# MCU.net
KiCad netlist of a schematic drawn in EAGLE
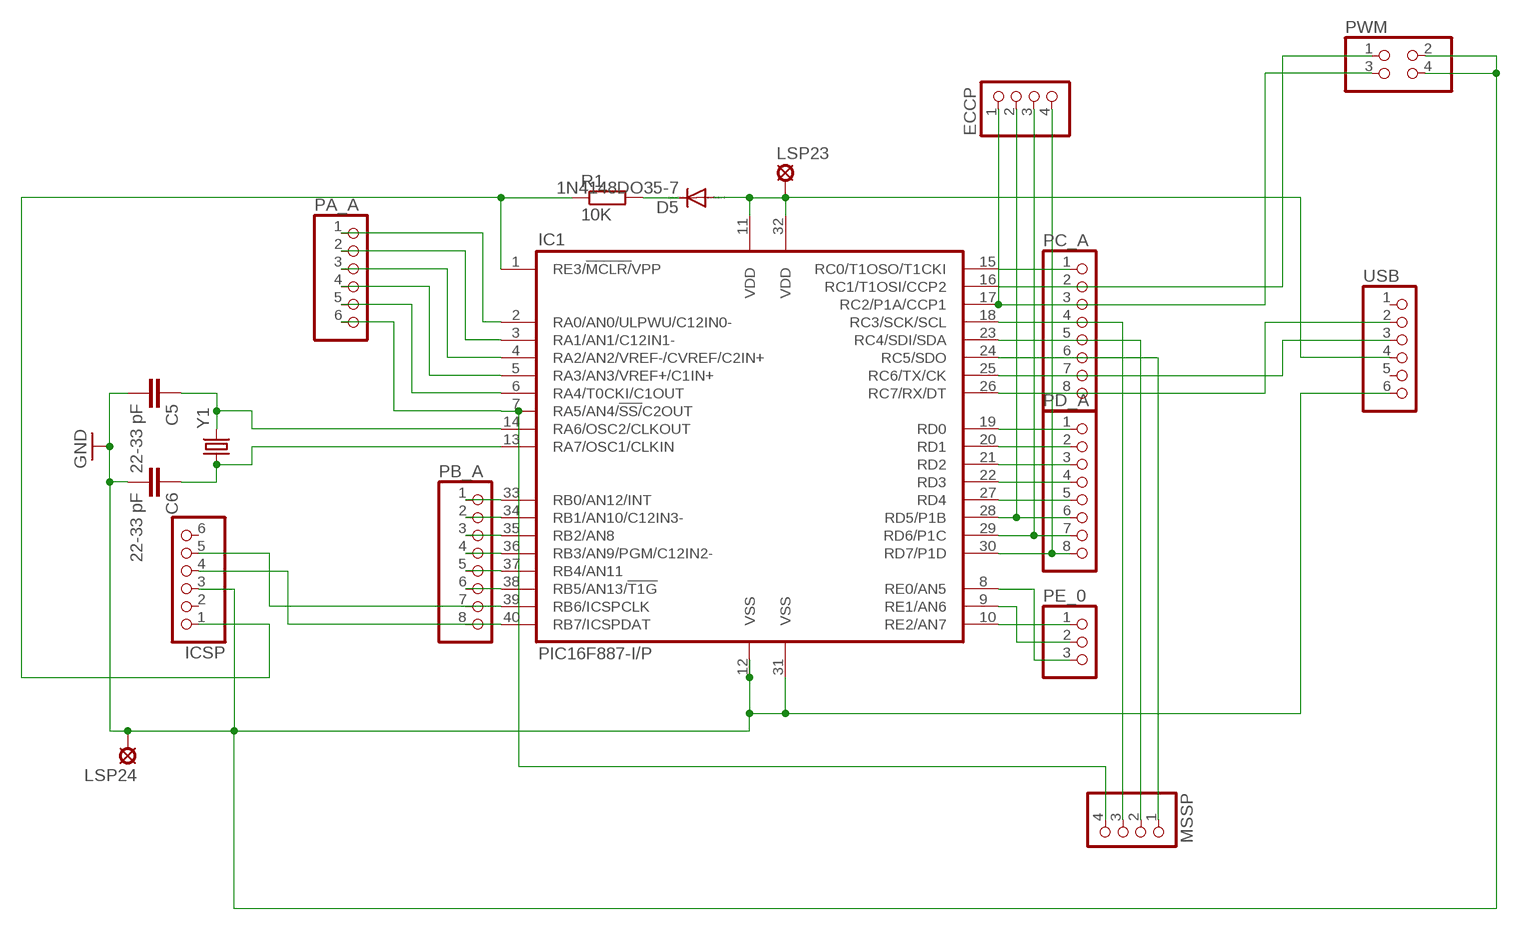
[diagram p0: schematic, sheet 1]

(export (version "E")
  (design (tool "Eeschema 10.0.6"))
  (components
    (comp (ref "C5")
      (value "22-33 pF")
      (footprint "eagle-import:C025-024X044")
      (libsource (lib "eagle-import") (part "C-EU025-024X044"))
    )
    (comp (ref "C6")
      (value "22-33 pF")
      (footprint "eagle-import:C025-024X044")
      (libsource (lib "eagle-import") (part "C-EU025-024X044"))
    )
    (comp (ref "D5")
      (value "1N4148DO35-7")
      (footprint "eagle-import:DO35-7")
      (libsource (lib "eagle-import") (part "1N4148DO35-7"))
    )
    (comp (ref "ECCP")
      (value "PINHD-1X4")
      (footprint "eagle-import:1X04")
      (libsource (lib "eagle-import") (part "PINHD-1X4"))
    )
    (comp (ref "IC1")
      (value "PIC16F887-I/P")
      (footprint "eagle-import:DIL40")
      (libsource (lib "eagle-import") (part "PIC16F887-I/P"))
    )
    (comp (ref "ICSP")
      (value "PINHD-1X6")
      (footprint "eagle-import:1X06")
      (libsource (lib "eagle-import") (part "PINHD-1X6"))
    )
    (comp (ref "LSP23")
      (value "LSP10")
      (footprint "eagle-import:LSP10")
      (libsource (lib "eagle-import") (part "LSP10"))
    )
    (comp (ref "LSP24")
      (value "LSP10")
      (footprint "eagle-import:LSP10")
      (libsource (lib "eagle-import") (part "LSP10"))
    )
    (comp (ref "MSSP")
      (value "PINHD-1X4")
      (footprint "eagle-import:1X04")
      (libsource (lib "eagle-import") (part "PINHD-1X4"))
    )
    (comp (ref "PA_A")
      (value "PINHD-1X6")
      (footprint "eagle-import:1X06")
      (libsource (lib "eagle-import") (part "PINHD-1X6"))
    )
    (comp (ref "PB_A")
      (value "PINHD-1X8")
      (footprint "eagle-import:1X08")
      (libsource (lib "eagle-import") (part "PINHD-1X8"))
    )
    (comp (ref "PC_A")
      (value "PINHD-1X8")
      (footprint "eagle-import:1X08")
      (libsource (lib "eagle-import") (part "PINHD-1X8"))
    )
    (comp (ref "PD_A")
      (value "PINHD-1X8")
      (footprint "eagle-import:1X08")
      (libsource (lib "eagle-import") (part "PINHD-1X8"))
    )
    (comp (ref "PE_0")
      (value "PINHD-1X3")
      (footprint "eagle-import:1X03")
      (libsource (lib "eagle-import") (part "PINHD-1X3"))
    )
    (comp (ref "PWM")
      (value "PINHD-2X2")
      (footprint "eagle-import:2X02")
      (libsource (lib "eagle-import") (part "PINHD-2X2"))
    )
    (comp (ref "R1")
      (value "10K")
      (footprint "eagle-import:0207_10")
      (libsource (lib "eagle-import") (part "R-EU_0207/10"))
    )
    (comp (ref "USB")
      (value "PINHD-1X6")
      (footprint "eagle-import:1X06")
      (libsource (lib "eagle-import") (part "PINHD-1X6"))
    )
    (comp (ref "Y1")
      (value "CRYSTALHC49UV")
      (footprint "eagle-import:HC49U-V")
      (libsource (lib "eagle-import") (part "CRYSTALHC49UV"))
    )
  )
  (nets
    (net (code "1") (name "GND") (class "Default")
      (node (ref "C5") (pin "2") (pinfunction "2_2") (pintype "passive"))
      (node (ref "C6") (pin "2") (pinfunction "2_2") (pintype "passive"))
      (node (ref "IC1") (pin "12") (pinfunction "VSS_12") (pintype "power_in"))
      (node (ref "IC1") (pin "31") (pinfunction "VSS_31") (pintype "power_in"))
      (node (ref "ICSP") (pin "3") (pinfunction "3_3") (pintype "passive"))
      (node (ref "LSP24") (pin "MP") (pinfunction "MP_MP") (pintype "passive"))
      (node (ref "PWM") (pin "2") (pinfunction "2_2") (pintype "passive"))
      (node (ref "PWM") (pin "4") (pinfunction "4_4") (pintype "passive"))
      (node (ref "USB") (pin "6") (pinfunction "6_6") (pintype "passive"))
    )
    (net (code "2") (name "Net-(D5-PadA)") (class "Default")
      (node (ref "D5") (pin "A") (pinfunction "A_A") (pintype "passive"))
      (node (ref "IC1") (pin "11") (pinfunction "VDD_11") (pintype "power_in"))
      (node (ref "IC1") (pin "32") (pinfunction "VDD_32") (pintype "power_in"))
      (node (ref "LSP23") (pin "MP") (pinfunction "MP_MP") (pintype "passive"))
      (node (ref "USB") (pin "4") (pinfunction "4_4") (pintype "passive"))
    )
    (net (code "3") (name "Net-(D5-PadC)") (class "Default")
      (node (ref "D5") (pin "C") (pinfunction "C_C") (pintype "passive"))
      (node (ref "R1") (pin "2") (pinfunction "2_2") (pintype "passive"))
    )
    (net (code "4") (name "Net-(IC1-RA0{slash}AN0{slash}ULPWU{slash}C12IN0-)") (class "Default")
      (node (ref "IC1") (pin "2") (pinfunction "RA0/AN0/ULPWU/C12IN0-_2") (pintype "bidirectional"))
      (node (ref "PA_A") (pin "1") (pinfunction "1_1") (pintype "passive"))
    )
    (net (code "5") (name "Net-(IC1-RA1{slash}AN1{slash}C12IN1-)") (class "Default")
      (node (ref "IC1") (pin "3") (pinfunction "RA1/AN1/C12IN1-_3") (pintype "bidirectional"))
      (node (ref "PA_A") (pin "2") (pinfunction "2_2") (pintype "passive"))
    )
    (net (code "6") (name "Net-(IC1-RA2{slash}AN2{slash}VREF-{slash}CVREF{slash}C2IN+)") (class "Default")
      (node (ref "IC1") (pin "4") (pinfunction "RA2/AN2/VREF-/CVREF/C2IN+_4") (pintype "bidirectional"))
      (node (ref "PA_A") (pin "3") (pinfunction "3_3") (pintype "passive"))
    )
    (net (code "7") (name "Net-(IC1-RA3{slash}AN3{slash}VREF+{slash}C1IN+)") (class "Default")
      (node (ref "IC1") (pin "5") (pinfunction "RA3/AN3/VREF+/C1IN+_5") (pintype "bidirectional"))
      (node (ref "PA_A") (pin "4") (pinfunction "4_4") (pintype "passive"))
    )
    (net (code "8") (name "Net-(IC1-RA4{slash}T0CKI{slash}C1OUT)") (class "Default")
      (node (ref "IC1") (pin "6") (pinfunction "RA4/T0CKI/C1OUT_6") (pintype "bidirectional"))
      (node (ref "PA_A") (pin "5") (pinfunction "5_5") (pintype "passive"))
    )
    (net (code "9") (name "Net-(IC1-RA5{slash}AN4{slash}~{SS{slash}}C2OUT)") (class "Default")
      (node (ref "IC1") (pin "7") (pinfunction "RA5/AN4/~{SS/}C2OUT_7") (pintype "bidirectional"))
      (node (ref "MSSP") (pin "4") (pinfunction "4_4") (pintype "passive"))
      (node (ref "PA_A") (pin "6") (pinfunction "6_6") (pintype "passive"))
    )
    (net (code "10") (name "Net-(IC1-RA6{slash}OSC2{slash}CLKOUT)") (class "Default")
      (node (ref "C5") (pin "1") (pinfunction "1_1") (pintype "passive"))
      (node (ref "IC1") (pin "14") (pinfunction "RA6/OSC2/CLKOUT_14") (pintype "bidirectional"))
      (node (ref "Y1") (pin "2") (pinfunction "2_2") (pintype "passive"))
    )
    (net (code "11") (name "Net-(IC1-RA7{slash}OSC1{slash}CLKIN)") (class "Default")
      (node (ref "C6") (pin "1") (pinfunction "1_1") (pintype "passive"))
      (node (ref "IC1") (pin "13") (pinfunction "RA7/OSC1/CLKIN_13") (pintype "bidirectional"))
      (node (ref "Y1") (pin "1") (pinfunction "1_1") (pintype "passive"))
    )
    (net (code "12") (name "Net-(IC1-RB0{slash}AN12{slash}INT)") (class "Default")
      (node (ref "IC1") (pin "33") (pinfunction "RB0/AN12/INT_33") (pintype "bidirectional"))
      (node (ref "PB_A") (pin "1") (pinfunction "1_1") (pintype "passive"))
    )
    (net (code "13") (name "Net-(IC1-RB1{slash}AN10{slash}C12IN3-)") (class "Default")
      (node (ref "IC1") (pin "34") (pinfunction "RB1/AN10/C12IN3-_34") (pintype "bidirectional"))
      (node (ref "PB_A") (pin "2") (pinfunction "2_2") (pintype "passive"))
    )
    (net (code "14") (name "Net-(IC1-RB2{slash}AN8)") (class "Default")
      (node (ref "IC1") (pin "35") (pinfunction "RB2/AN8_35") (pintype "bidirectional"))
      (node (ref "PB_A") (pin "3") (pinfunction "3_3") (pintype "passive"))
    )
    (net (code "15") (name "Net-(IC1-RB3{slash}AN9{slash}PGM{slash}C12IN2-)") (class "Default")
      (node (ref "IC1") (pin "36") (pinfunction "RB3/AN9/PGM/C12IN2-_36") (pintype "bidirectional"))
      (node (ref "PB_A") (pin "4") (pinfunction "4_4") (pintype "passive"))
    )
    (net (code "16") (name "Net-(IC1-RB4{slash}AN11)") (class "Default")
      (node (ref "IC1") (pin "37") (pinfunction "RB4/AN11_37") (pintype "bidirectional"))
      (node (ref "PB_A") (pin "5") (pinfunction "5_5") (pintype "passive"))
    )
    (net (code "17") (name "Net-(IC1-RB5{slash}AN13{slash}~{T1G})") (class "Default")
      (node (ref "IC1") (pin "38") (pinfunction "RB5/AN13/~{T1G}_38") (pintype "bidirectional"))
      (node (ref "PB_A") (pin "6") (pinfunction "6_6") (pintype "passive"))
    )
    (net (code "18") (name "Net-(IC1-RB6{slash}ICSPCLK)") (class "Default")
      (node (ref "IC1") (pin "39") (pinfunction "RB6/ICSPCLK_39") (pintype "bidirectional"))
      (node (ref "ICSP") (pin "5") (pinfunction "5_5") (pintype "passive"))
      (node (ref "PB_A") (pin "7") (pinfunction "7_7") (pintype "passive"))
    )
    (net (code "19") (name "Net-(IC1-RB7{slash}ICSPDAT)") (class "Default")
      (node (ref "IC1") (pin "40") (pinfunction "RB7/ICSPDAT_40") (pintype "bidirectional"))
      (node (ref "ICSP") (pin "4") (pinfunction "4_4") (pintype "passive"))
      (node (ref "PB_A") (pin "8") (pinfunction "8_8") (pintype "passive"))
    )
    (net (code "20") (name "Net-(IC1-RC0{slash}T1OSO{slash}T1CKI)") (class "Default")
      (node (ref "IC1") (pin "15") (pinfunction "RC0/T1OSO/T1CKI_15") (pintype "bidirectional"))
      (node (ref "PC_A") (pin "1") (pinfunction "1_1") (pintype "passive"))
    )
    (net (code "21") (name "Net-(IC1-RC1{slash}T1OSI{slash}CCP2)") (class "Default")
      (node (ref "IC1") (pin "16") (pinfunction "RC1/T1OSI/CCP2_16") (pintype "bidirectional"))
      (node (ref "PC_A") (pin "2") (pinfunction "2_2") (pintype "passive"))
      (node (ref "PWM") (pin "1") (pinfunction "1_1") (pintype "passive"))
    )
    (net (code "22") (name "Net-(IC1-RC2{slash}P1A{slash}CCP1)") (class "Default")
      (node (ref "ECCP") (pin "1") (pinfunction "1_1") (pintype "passive"))
      (node (ref "IC1") (pin "17") (pinfunction "RC2/P1A/CCP1_17") (pintype "bidirectional"))
      (node (ref "PC_A") (pin "3") (pinfunction "3_3") (pintype "passive"))
      (node (ref "PWM") (pin "3") (pinfunction "3_3") (pintype "passive"))
    )
    (net (code "23") (name "Net-(IC1-RC3{slash}SCK{slash}SCL)") (class "Default")
      (node (ref "IC1") (pin "18") (pinfunction "RC3/SCK/SCL_18") (pintype "bidirectional"))
      (node (ref "MSSP") (pin "3") (pinfunction "3_3") (pintype "passive"))
      (node (ref "PC_A") (pin "4") (pinfunction "4_4") (pintype "passive"))
    )
    (net (code "24") (name "Net-(IC1-RC4{slash}SDI{slash}SDA)") (class "Default")
      (node (ref "IC1") (pin "23") (pinfunction "RC4/SDI/SDA_23") (pintype "bidirectional"))
      (node (ref "MSSP") (pin "2") (pinfunction "2_2") (pintype "passive"))
      (node (ref "PC_A") (pin "5") (pinfunction "5_5") (pintype "passive"))
    )
    (net (code "25") (name "Net-(IC1-RC5{slash}SDO)") (class "Default")
      (node (ref "IC1") (pin "24") (pinfunction "RC5/SDO_24") (pintype "bidirectional"))
      (node (ref "MSSP") (pin "1") (pinfunction "1_1") (pintype "passive"))
      (node (ref "PC_A") (pin "6") (pinfunction "6_6") (pintype "passive"))
    )
    (net (code "26") (name "Net-(IC1-RC6{slash}TX{slash}CK)") (class "Default")
      (node (ref "IC1") (pin "25") (pinfunction "RC6/TX/CK_25") (pintype "bidirectional"))
      (node (ref "PC_A") (pin "7") (pinfunction "7_7") (pintype "passive"))
      (node (ref "USB") (pin "3") (pinfunction "3_3") (pintype "passive"))
    )
    (net (code "27") (name "Net-(IC1-RC7{slash}RX{slash}DT)") (class "Default")
      (node (ref "IC1") (pin "26") (pinfunction "RC7/RX/DT_26") (pintype "bidirectional"))
      (node (ref "PC_A") (pin "8") (pinfunction "8_8") (pintype "passive"))
      (node (ref "USB") (pin "2") (pinfunction "2_2") (pintype "passive"))
    )
    (net (code "28") (name "Net-(IC1-RD0)") (class "Default")
      (node (ref "IC1") (pin "19") (pinfunction "RD0_19") (pintype "bidirectional"))
      (node (ref "PD_A") (pin "1") (pinfunction "1_1") (pintype "passive"))
    )
    (net (code "29") (name "Net-(IC1-RD1)") (class "Default")
      (node (ref "IC1") (pin "20") (pinfunction "RD1_20") (pintype "bidirectional"))
      (node (ref "PD_A") (pin "2") (pinfunction "2_2") (pintype "passive"))
    )
    (net (code "30") (name "Net-(IC1-RD2)") (class "Default")
      (node (ref "IC1") (pin "21") (pinfunction "RD2_21") (pintype "bidirectional"))
      (node (ref "PD_A") (pin "3") (pinfunction "3_3") (pintype "passive"))
    )
    (net (code "31") (name "Net-(IC1-RD3)") (class "Default")
      (node (ref "IC1") (pin "22") (pinfunction "RD3_22") (pintype "bidirectional"))
      (node (ref "PD_A") (pin "4") (pinfunction "4_4") (pintype "passive"))
    )
    (net (code "32") (name "Net-(IC1-RD4)") (class "Default")
      (node (ref "IC1") (pin "27") (pinfunction "RD4_27") (pintype "bidirectional"))
      (node (ref "PD_A") (pin "5") (pinfunction "5_5") (pintype "passive"))
    )
    (net (code "33") (name "Net-(IC1-RD5{slash}P1B)") (class "Default")
      (node (ref "ECCP") (pin "2") (pinfunction "2_2") (pintype "passive"))
      (node (ref "IC1") (pin "28") (pinfunction "RD5/P1B_28") (pintype "bidirectional"))
      (node (ref "PD_A") (pin "6") (pinfunction "6_6") (pintype "passive"))
    )
    (net (code "34") (name "Net-(IC1-RD6{slash}P1C)") (class "Default")
      (node (ref "ECCP") (pin "3") (pinfunction "3_3") (pintype "passive"))
      (node (ref "IC1") (pin "29") (pinfunction "RD6/P1C_29") (pintype "bidirectional"))
      (node (ref "PD_A") (pin "7") (pinfunction "7_7") (pintype "passive"))
    )
    (net (code "35") (name "Net-(IC1-RD7{slash}P1D)") (class "Default")
      (node (ref "ECCP") (pin "4") (pinfunction "4_4") (pintype "passive"))
      (node (ref "IC1") (pin "30") (pinfunction "RD7/P1D_30") (pintype "bidirectional"))
      (node (ref "PD_A") (pin "8") (pinfunction "8_8") (pintype "passive"))
    )
    (net (code "36") (name "Net-(IC1-RE0{slash}AN5)") (class "Default")
      (node (ref "IC1") (pin "8") (pinfunction "RE0/AN5_8") (pintype "bidirectional"))
      (node (ref "PE_0") (pin "3") (pinfunction "3_3") (pintype "passive"))
    )
    (net (code "37") (name "Net-(IC1-RE1{slash}AN6)") (class "Default")
      (node (ref "IC1") (pin "9") (pinfunction "RE1/AN6_9") (pintype "bidirectional"))
      (node (ref "PE_0") (pin "2") (pinfunction "2_2") (pintype "passive"))
    )
    (net (code "38") (name "Net-(IC1-RE2{slash}AN7)") (class "Default")
      (node (ref "IC1") (pin "10") (pinfunction "RE2/AN7_10") (pintype "bidirectional"))
      (node (ref "PE_0") (pin "1") (pinfunction "1_1") (pintype "passive"))
    )
    (net (code "39") (name "Net-(IC1-RE3{slash}~{MCLR{slash}}VPP)") (class "Default")
      (node (ref "IC1") (pin "1") (pinfunction "RE3/~{MCLR/}VPP_1") (pintype "input"))
      (node (ref "ICSP") (pin "1") (pinfunction "1_1") (pintype "passive"))
      (node (ref "R1") (pin "1") (pinfunction "1_1") (pintype "passive"))
    )
    (net (code "40") (name "unconnected-(ICSP-Pad2)") (class "Default")
      (node (ref "ICSP") (pin "2") (pinfunction "2_2") (pintype "passive"))
    )
    (net (code "41") (name "unconnected-(ICSP-Pad6)") (class "Default")
      (node (ref "ICSP") (pin "6") (pinfunction "6_6") (pintype "passive"))
    )
    (net (code "42") (name "unconnected-(USB-Pad1)") (class "Default")
      (node (ref "USB") (pin "1") (pinfunction "1_1") (pintype "passive"))
    )
    (net (code "43") (name "unconnected-(USB-Pad5)") (class "Default")
      (node (ref "USB") (pin "5") (pinfunction "5_5") (pintype "passive"))
    )
  )
)
